# ADS124S08.net
KiCad netlist of a schematic drawn in EAGLE
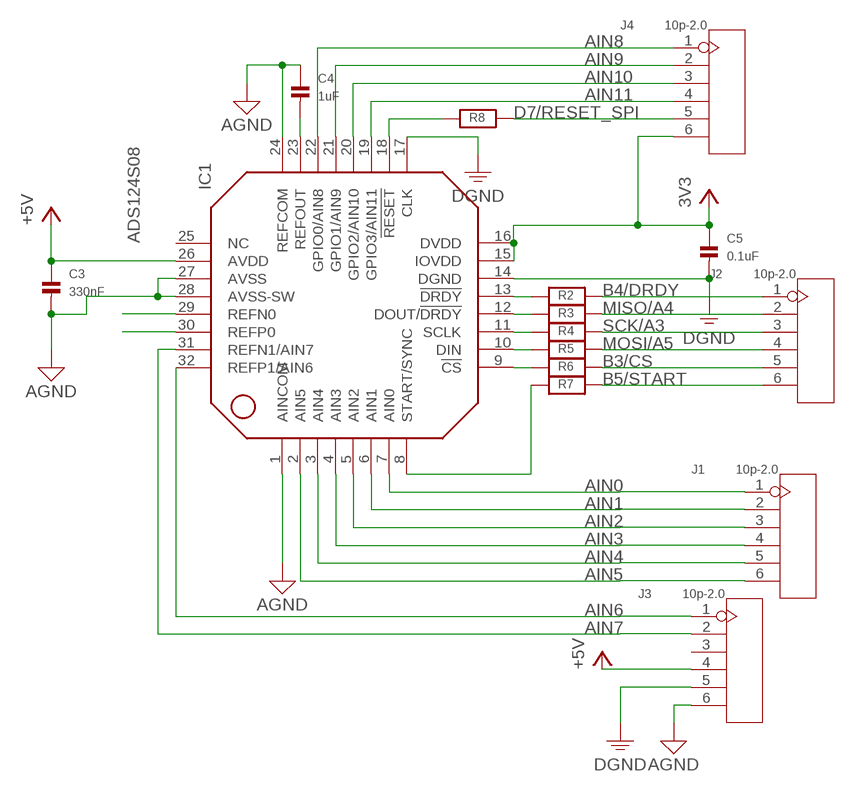
[diagram p0: schematic, sheet 1]

(export (version "E")
  (design (tool "Eeschema 10.0.6"))
  (components
    (comp (ref "C3")
      (value "330nF")
      (footprint "eagle-import:0805")
      (fields (field (name "MF") "AVX") (field (name "MPN") "08055C104JAT2A"))
      (libsource (lib "eagle-import") (part "CAP_CERAMIC0805"))
    )
    (comp (ref "C4")
      (value "1uF")
      (footprint "eagle-import:0805")
      (fields (field (name "MF") "AVX") (field (name "MPN") "08055C104JAT2A"))
      (libsource (lib "eagle-import") (part "CAP_CERAMIC0805"))
    )
    (comp (ref "C5")
      (value "0.1uF")
      (footprint "eagle-import:0805")
      (fields (field (name "MF") "AVX") (field (name "MPN") "08055C104JAT2A"))
      (libsource (lib "eagle-import") (part "CAP_CERAMIC0805"))
    )
    (comp (ref "IC1")
      (value "ADS124S08")
      (footprint "eagle-import:ADS124S08")
      (libsource (lib "eagle-import") (part "ADS124S08"))
    )
    (comp (ref "J1")
      (value "10p-2.0")
      (footprint "eagle-import:H10-2.0")
      (fields (field (name "MPN") "F243-1110A1BSUA1"))
      (libsource (lib "eagle-import") (part "DIP-BLACK-FEMALE-HEADER-VERT(10P-2.0)"))
    )
    (comp (ref "J2")
      (value "10p-2.0")
      (footprint "eagle-import:H10-2.0")
      (fields (field (name "MPN") "F243-1110A1BSUA1"))
      (libsource (lib "eagle-import") (part "DIP-BLACK-FEMALE-HEADER-VERT(10P-2.0)"))
    )
    (comp (ref "J3")
      (value "10p-2.0")
      (footprint "eagle-import:H10-2.0")
      (fields (field (name "MPN") "F243-1110A1BSUA1"))
      (libsource (lib "eagle-import") (part "DIP-BLACK-FEMALE-HEADER-VERT(10P-2.0)"))
    )
    (comp (ref "J4")
      (value "10p-2.0")
      (footprint "eagle-import:H10-2.0")
      (fields (field (name "MPN") "F243-1110A1BSUA1"))
      (libsource (lib "eagle-import") (part "DIP-BLACK-FEMALE-HEADER-VERT(10P-2.0)"))
    )
    (comp (ref "R2")
      (value "47")
      (footprint "eagle-import:0603")
      (libsource (lib "eagle-import") (part "RESISTOR0603"))
    )
    (comp (ref "R3")
      (value "47")
      (footprint "eagle-import:0603")
      (libsource (lib "eagle-import") (part "RESISTOR0603"))
    )
    (comp (ref "R4")
      (value "47")
      (footprint "eagle-import:0603")
      (libsource (lib "eagle-import") (part "RESISTOR0603"))
    )
    (comp (ref "R5")
      (value "47")
      (footprint "eagle-import:0603")
      (libsource (lib "eagle-import") (part "RESISTOR0603"))
    )
    (comp (ref "R6")
      (value "RESISTOR0603")
      (footprint "eagle-import:0603")
      (libsource (lib "eagle-import") (part "RESISTOR0603"))
    )
    (comp (ref "R7")
      (value "47")
      (footprint "eagle-import:0603")
      (libsource (lib "eagle-import") (part "RESISTOR0603"))
    )
    (comp (ref "R8")
      (value "47")
      (footprint "eagle-import:0603")
      (libsource (lib "eagle-import") (part "RESISTOR0603"))
    )
  )
  (nets
    (net (code "1") (name "+5V") (class "Default")
      (node (ref "C3") (pin "1") (pinfunction "P$1_1") (pintype "passive"))
      (node (ref "IC1") (pin "26") (pinfunction "AVDD_26") (pintype "bidirectional"))
      (node (ref "J3") (pin "4") (pinfunction "4_4") (pintype "bidirectional"))
    )
    (net (code "2") (name "/AIN0") (class "Default")
      (node (ref "IC1") (pin "7") (pinfunction "AIN0_7") (pintype "bidirectional"))
      (node (ref "J1") (pin "1") (pinfunction "1_1") (pintype "bidirectional"))
    )
    (net (code "3") (name "/AIN1") (class "Default")
      (node (ref "IC1") (pin "6") (pinfunction "AIN1_6") (pintype "bidirectional"))
      (node (ref "J1") (pin "2") (pinfunction "2_2") (pintype "bidirectional"))
    )
    (net (code "4") (name "/AIN2") (class "Default")
      (node (ref "IC1") (pin "5") (pinfunction "AIN2_5") (pintype "bidirectional"))
      (node (ref "J1") (pin "3") (pinfunction "3_3") (pintype "bidirectional"))
    )
    (net (code "5") (name "/AIN3") (class "Default")
      (node (ref "IC1") (pin "4") (pinfunction "AIN3_4") (pintype "power_in"))
      (node (ref "J1") (pin "4") (pinfunction "4_4") (pintype "bidirectional"))
    )
    (net (code "6") (name "/AIN4") (class "Default")
      (node (ref "IC1") (pin "3") (pinfunction "AIN4_3") (pintype "bidirectional"))
      (node (ref "J1") (pin "5") (pinfunction "5_5") (pintype "bidirectional"))
    )
    (net (code "7") (name "/AIN5") (class "Default")
      (node (ref "IC1") (pin "2") (pinfunction "AIN5_2") (pintype "bidirectional"))
      (node (ref "J1") (pin "6") (pinfunction "6_6") (pintype "bidirectional"))
    )
    (net (code "8") (name "/AIN6") (class "Default")
      (node (ref "IC1") (pin "32") (pinfunction "REFP1/AIN6_32") (pintype "bidirectional"))
      (node (ref "J3") (pin "1") (pinfunction "1_1") (pintype "bidirectional"))
    )
    (net (code "9") (name "/AIN7") (class "Default")
      (node (ref "IC1") (pin "31") (pinfunction "REFN1/AIN7_31") (pintype "bidirectional"))
      (node (ref "J3") (pin "2") (pinfunction "2_2") (pintype "bidirectional"))
    )
    (net (code "10") (name "/AIN8") (class "Default")
      (node (ref "IC1") (pin "22") (pinfunction "GPIO0/AIN8_22") (pintype "bidirectional"))
      (node (ref "J4") (pin "1") (pinfunction "1_1") (pintype "bidirectional"))
    )
    (net (code "11") (name "/AIN9") (class "Default")
      (node (ref "IC1") (pin "21") (pinfunction "GPIO1/AIN9_21") (pintype "bidirectional"))
      (node (ref "J4") (pin "2") (pinfunction "2_2") (pintype "bidirectional"))
    )
    (net (code "12") (name "/AIN10") (class "Default")
      (node (ref "IC1") (pin "20") (pinfunction "GPIO2/AIN10_20") (pintype "bidirectional"))
      (node (ref "J4") (pin "3") (pinfunction "3_3") (pintype "bidirectional"))
    )
    (net (code "13") (name "/AIN11") (class "Default")
      (node (ref "IC1") (pin "19") (pinfunction "GPIO3/AIN11_19") (pintype "bidirectional"))
      (node (ref "J4") (pin "4") (pinfunction "4_4") (pintype "bidirectional"))
    )
    (net (code "14") (name "/B3{slash}CS") (class "Default")
      (node (ref "J2") (pin "5") (pinfunction "5_5") (pintype "bidirectional"))
      (node (ref "R6") (pin "2") (pinfunction "2_2") (pintype "passive"))
    )
    (net (code "15") (name "/B4{slash}DRDY") (class "Default")
      (node (ref "J2") (pin "1") (pinfunction "1_1") (pintype "bidirectional"))
      (node (ref "R2") (pin "2") (pinfunction "2_2") (pintype "passive"))
    )
    (net (code "16") (name "/B5{slash}START") (class "Default")
      (node (ref "J2") (pin "6") (pinfunction "6_6") (pintype "bidirectional"))
      (node (ref "R7") (pin "2") (pinfunction "2_2") (pintype "passive"))
    )
    (net (code "17") (name "/D7{slash}RESET_SPI") (class "Default")
      (node (ref "J4") (pin "5") (pinfunction "5_5") (pintype "bidirectional"))
      (node (ref "R8") (pin "2") (pinfunction "2_2") (pintype "passive"))
    )
    (net (code "18") (name "/MISO{slash}A4") (class "Default")
      (node (ref "J2") (pin "2") (pinfunction "2_2") (pintype "bidirectional"))
      (node (ref "R3") (pin "2") (pinfunction "2_2") (pintype "passive"))
    )
    (net (code "19") (name "/MOSI{slash}A5") (class "Default")
      (node (ref "J2") (pin "4") (pinfunction "4_4") (pintype "bidirectional"))
      (node (ref "R5") (pin "2") (pinfunction "2_2") (pintype "passive"))
    )
    (net (code "20") (name "/SCK{slash}A3") (class "Default")
      (node (ref "J2") (pin "3") (pinfunction "3_3") (pintype "bidirectional"))
      (node (ref "R4") (pin "2") (pinfunction "2_2") (pintype "passive"))
    )
    (net (code "21") (name "3V3") (class "Default")
      (node (ref "C5") (pin "1") (pinfunction "P$1_1") (pintype "passive"))
      (node (ref "IC1") (pin "15") (pinfunction "IOVDD_15") (pintype "bidirectional"))
      (node (ref "IC1") (pin "16") (pinfunction "DVDD_16") (pintype "bidirectional"))
      (node (ref "J4") (pin "6") (pinfunction "6_6") (pintype "bidirectional"))
    )
    (net (code "22") (name "AGND") (class "Default")
      (node (ref "C3") (pin "2") (pinfunction "P$2_2") (pintype "passive"))
      (node (ref "C4") (pin "1") (pinfunction "P$1_1") (pintype "passive"))
      (node (ref "IC1") (pin "1") (pinfunction "AINCOM_1") (pintype "bidirectional"))
      (node (ref "IC1") (pin "24") (pinfunction "REFCOM_24") (pintype "bidirectional"))
      (node (ref "IC1") (pin "27") (pinfunction "AVSS_27") (pintype "bidirectional"))
      (node (ref "IC1") (pin "28") (pinfunction "AVSS-SW_28") (pintype "bidirectional"))
      (node (ref "J3") (pin "6") (pinfunction "6_6") (pintype "bidirectional"))
    )
    (net (code "23") (name "DGND") (class "Default")
      (node (ref "C5") (pin "2") (pinfunction "P$2_2") (pintype "passive"))
      (node (ref "IC1") (pin "14") (pinfunction "DGND_14") (pintype "bidirectional"))
      (node (ref "IC1") (pin "17") (pinfunction "CLK_17") (pintype "bidirectional"))
      (node (ref "J3") (pin "5") (pinfunction "5_5") (pintype "bidirectional"))
    )
    (net (code "24") (name "Net-(C4-P$2)") (class "Default")
      (node (ref "C4") (pin "2") (pinfunction "P$2_2") (pintype "passive"))
      (node (ref "IC1") (pin "23") (pinfunction "REFOUT_23") (pintype "power_in"))
    )
    (net (code "25") (name "Net-(IC1-DIN)") (class "Default")
      (node (ref "IC1") (pin "10") (pinfunction "DIN_10") (pintype "bidirectional"))
      (node (ref "R5") (pin "1") (pinfunction "1_1") (pintype "passive"))
    )
    (net (code "26") (name "Net-(IC1-DOUT{slash}~{DRDY})") (class "Default")
      (node (ref "IC1") (pin "12") (pinfunction "DOUT/~{DRDY}_12") (pintype "bidirectional"))
      (node (ref "R3") (pin "1") (pinfunction "1_1") (pintype "passive"))
    )
    (net (code "27") (name "Net-(IC1-SCLK)") (class "Default")
      (node (ref "IC1") (pin "11") (pinfunction "SCLK_11") (pintype "bidirectional"))
      (node (ref "R4") (pin "1") (pinfunction "1_1") (pintype "passive"))
    )
    (net (code "28") (name "Net-(IC1-START{slash}SYNC)") (class "Default")
      (node (ref "IC1") (pin "8") (pinfunction "START/SYNC_8") (pintype "bidirectional"))
      (node (ref "R7") (pin "1") (pinfunction "1_1") (pintype "passive"))
    )
    (net (code "29") (name "Net-(IC1-~{CS})") (class "Default")
      (node (ref "IC1") (pin "9") (pinfunction "~{CS}_9") (pintype "bidirectional"))
      (node (ref "R6") (pin "1") (pinfunction "1_1") (pintype "passive"))
    )
    (net (code "30") (name "Net-(IC1-~{DRDY})") (class "Default")
      (node (ref "IC1") (pin "13") (pinfunction "~{DRDY}_13") (pintype "bidirectional"))
      (node (ref "R2") (pin "1") (pinfunction "1_1") (pintype "passive"))
    )
    (net (code "31") (name "Net-(IC1-~{RESET})") (class "Default")
      (node (ref "IC1") (pin "18") (pinfunction "~{RESET}_18") (pintype "power_in"))
      (node (ref "R8") (pin "1") (pinfunction "1_1") (pintype "passive"))
    )
    (net (code "32") (name "unconnected-(IC1-NC-Pad25)") (class "Default")
      (node (ref "IC1") (pin "25") (pinfunction "NC_25") (pintype "bidirectional"))
    )
    (net (code "33") (name "unconnected-(IC1-REFN0-Pad29)") (class "Default")
      (node (ref "IC1") (pin "29") (pinfunction "REFN0_29") (pintype "bidirectional"))
    )
    (net (code "34") (name "unconnected-(IC1-REFP0-Pad30)") (class "Default")
      (node (ref "IC1") (pin "30") (pinfunction "REFP0_30") (pintype "bidirectional"))
    )
    (net (code "35") (name "unconnected-(J3-Pad3)") (class "Default")
      (node (ref "J3") (pin "3") (pinfunction "3_3") (pintype "bidirectional"))
    )
  )
)
